# Generator.net
KiCad netlist of a schematic drawn in Altium Designer
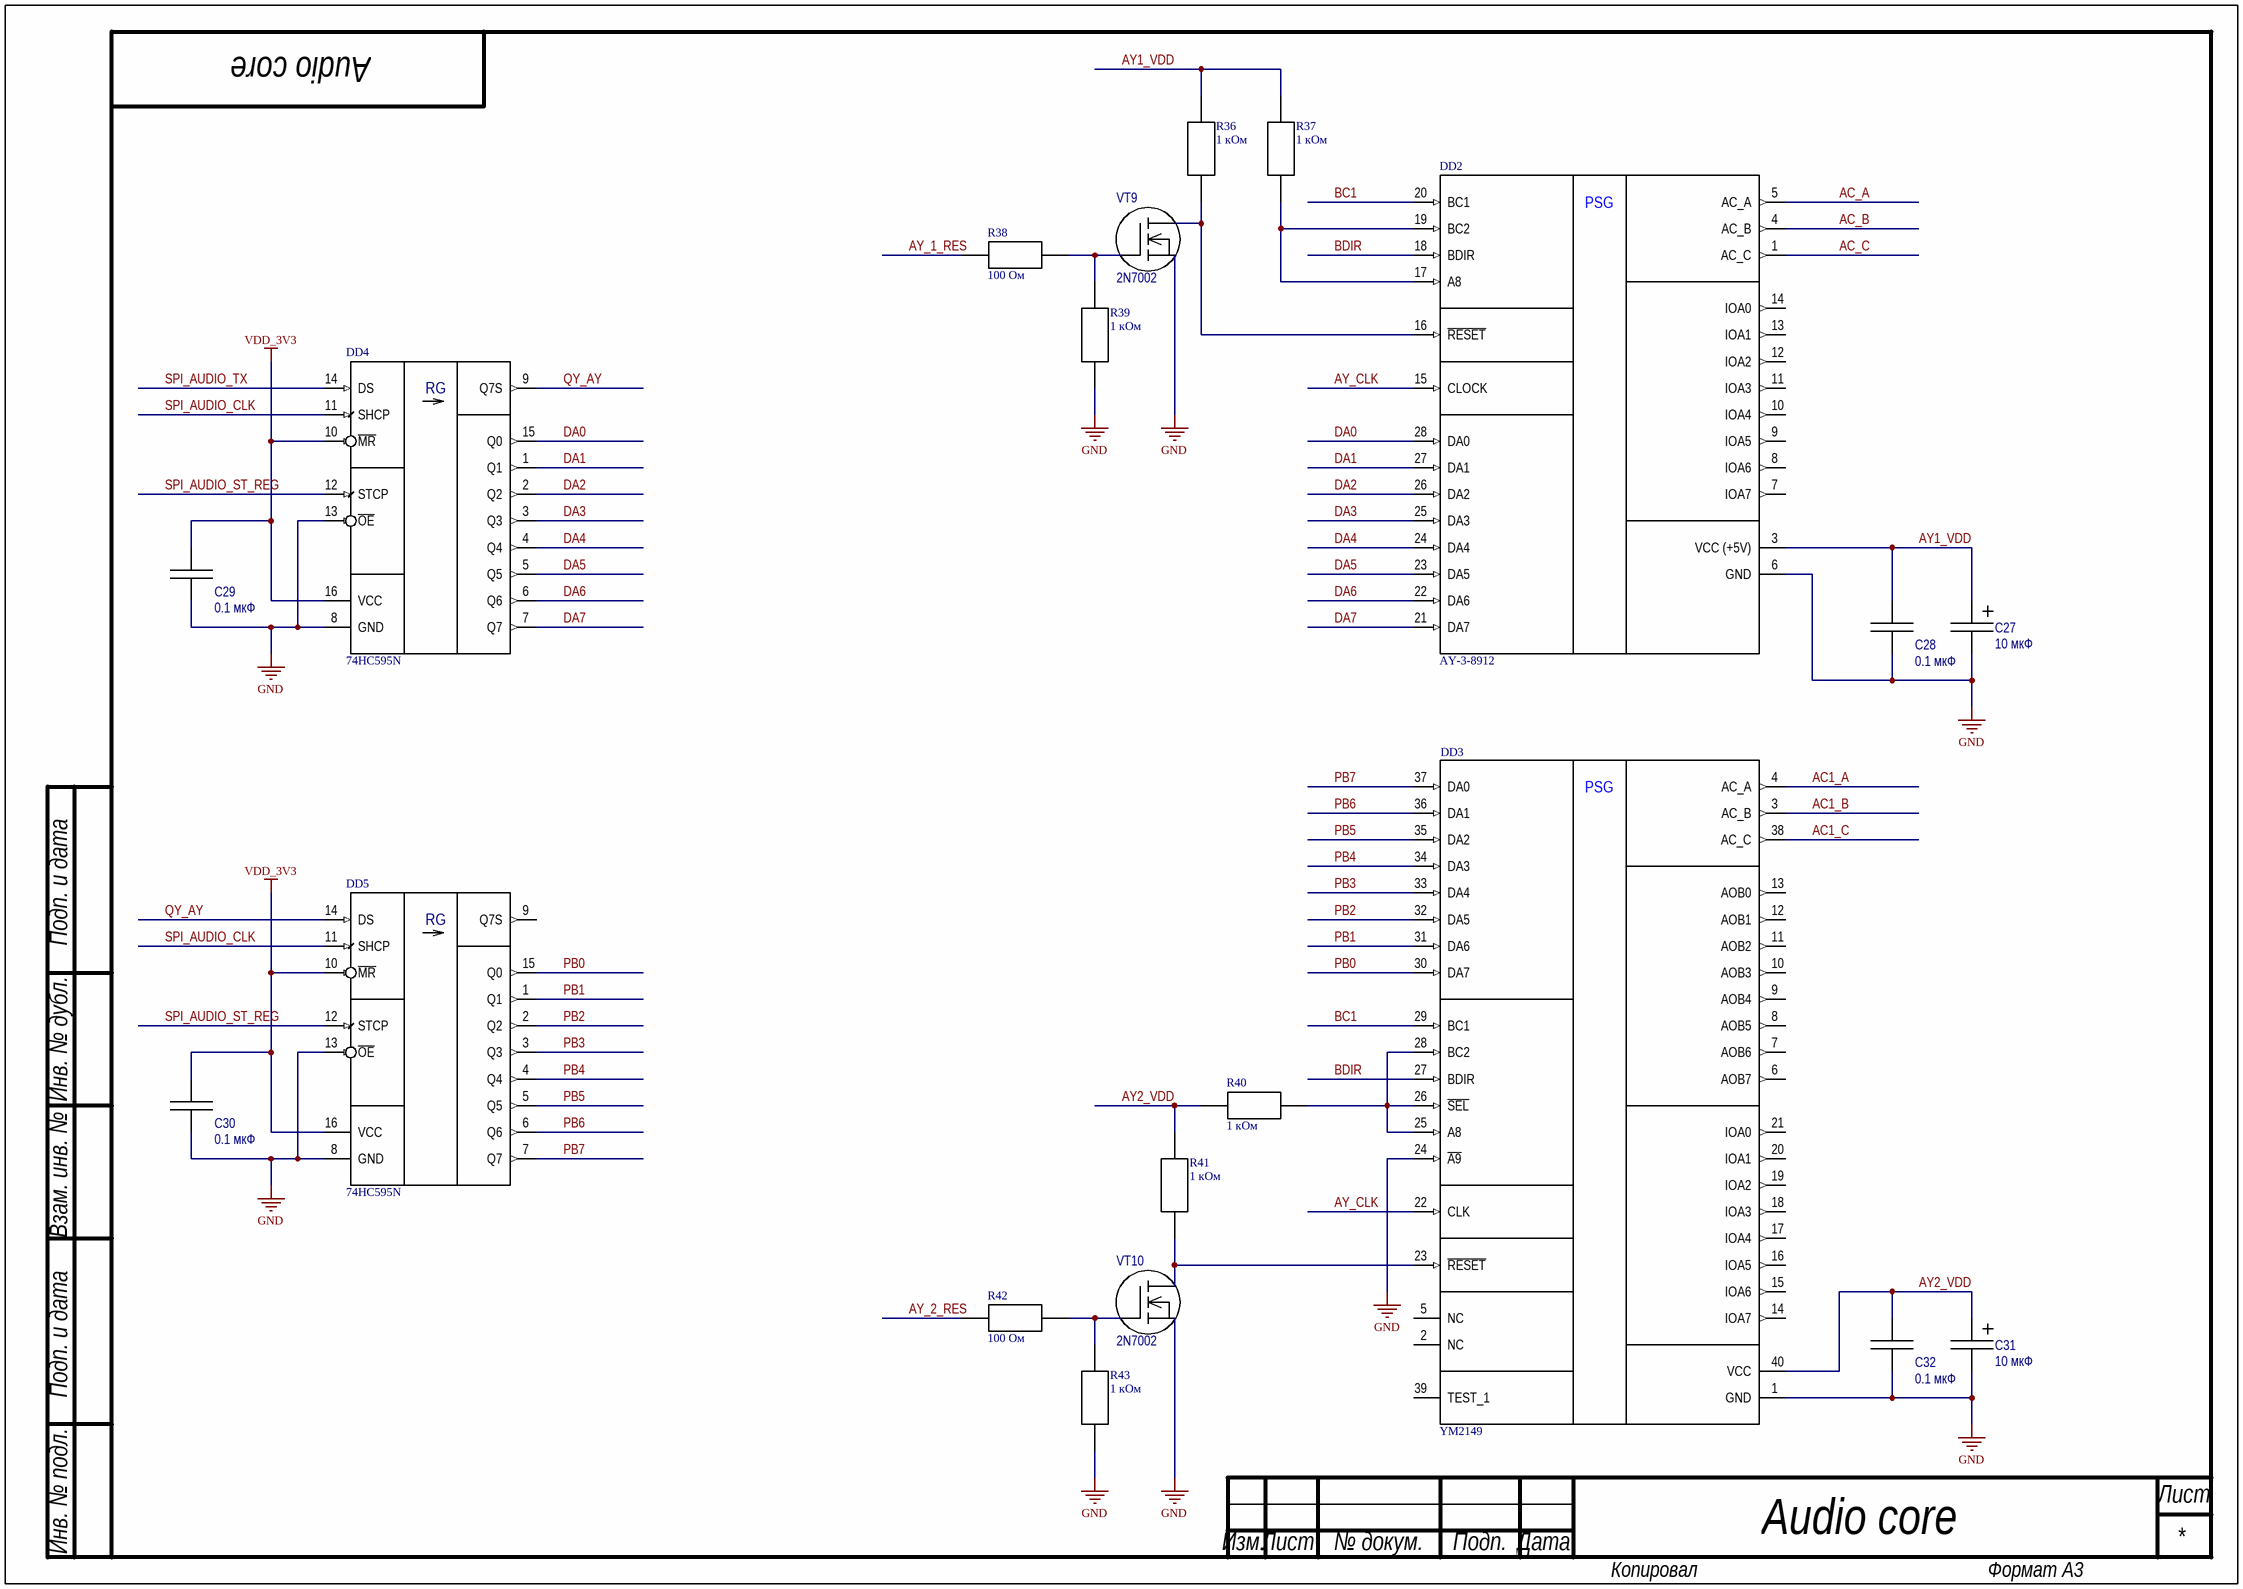
[diagram p0: Generator.SchDoc]

(export (version "E")
  (design (tool "Eeschema 10.0.6"))
  (components
    (comp (ref "C27")
      (value "10 мкФ")
      (footprint "C TAN_C")
      (description "SMD Tantalium Capacitor C")
      (fields
        (field (name "TOLERANCE") "/Укажите допуск в процентах/")
        (field (name "MANUFACTURER") "/Укажите компанию-производителя/")
      )
      (libsource (lib "my_lib") (part "CAP TAN_C"))
    )
    (comp (ref "C28")
      (value "0.1 мкФ")
      (footprint "C 1206")
      (description "SMD Capacitor 1206")
      (fields
        (field (name "TOLERANCE") "/Укажите допуск в процентах/")
        (field (name "MANUFACTURER") "/Укажите компанию-производителя/")
      )
      (libsource (lib "my_lib") (part "CAP 1206"))
    )
    (comp (ref "C29")
      (value "0.1 мкФ")
      (footprint "C 1206")
      (description "SMD Capacitor 1206")
      (fields
        (field (name "TOLERANCE") "/Укажите допуск в процентах/")
        (field (name "MANUFACTURER") "/Укажите компанию-производителя/")
      )
      (libsource (lib "my_lib") (part "CAP 1206"))
    )
    (comp (ref "C30")
      (value "0.1 мкФ")
      (footprint "C 1206")
      (description "SMD Capacitor 1206")
      (fields
        (field (name "TOLERANCE") "/Укажите допуск в процентах/")
        (field (name "MANUFACTURER") "/Укажите компанию-производителя/")
      )
      (libsource (lib "my_lib") (part "CAP 1206"))
    )
    (comp (ref "C31")
      (value "10 мкФ")
      (footprint "C TAN_C")
      (description "SMD Tantalium Capacitor C")
      (fields
        (field (name "TOLERANCE") "/Укажите допуск в процентах/")
        (field (name "MANUFACTURER") "/Укажите компанию-производителя/")
      )
      (libsource (lib "my_lib") (part "CAP TAN_C"))
    )
    (comp (ref "C32")
      (value "0.1 мкФ")
      (footprint "C 1206")
      (description "SMD Capacitor 1206")
      (fields
        (field (name "TOLERANCE") "/Укажите допуск в процентах/")
        (field (name "MANUFACTURER") "/Укажите компанию-производителя/")
      )
      (libsource (lib "my_lib") (part "CAP 1206"))
    )
    (comp (ref "DD2") (value "AY-3-8912") (footprint "DIP-28") (libsource (lib "my_lib") (part "AY-3-8912")))
    (comp (ref "DD3") (value "YM2149") (footprint "DIP-40") (libsource (lib "my_lib") (part "YM2149")))
    (comp (ref "DD4") (value "74HC595N") (footprint "SO16") (libsource (lib "my_lib") (part "74HC595N")))
    (comp (ref "DD5") (value "74HC595N") (footprint "SO16") (libsource (lib "my_lib") (part "74HC595N")))
    (comp (ref "R36") (value "1 кОм") (footprint "RES 0805") (libsource (lib "my_lib") (part "RES 0805")))
    (comp (ref "R37") (value "1 кОм") (footprint "RES 0805") (libsource (lib "my_lib") (part "RES 0805")))
    (comp (ref "R38") (value "100 Ом") (footprint "RES 0805") (libsource (lib "my_lib") (part "RES 0805")))
    (comp (ref "R39") (value "1 кОм") (footprint "RES 0805") (libsource (lib "my_lib") (part "RES 0805")))
    (comp (ref "R40") (value "1 кОм") (footprint "RES 0805") (libsource (lib "my_lib") (part "RES 0805")))
    (comp (ref "R41") (value "1 кОм") (footprint "RES 0805") (libsource (lib "my_lib") (part "RES 0805")))
    (comp (ref "R42") (value "100 Ом") (footprint "RES 0805") (libsource (lib "my_lib") (part "RES 0805")))
    (comp (ref "R43") (value "1 кОм") (footprint "RES 0805") (libsource (lib "my_lib") (part "RES 0805")))
    (comp (ref "VT9")
      (value "2N7002")
      (footprint "SOT-23")
      (description "60 V, 300 mA N-channel Trench MOSFET")
      (fields (field (name "MANUFACTURER") "NXP"))
      (libsource (lib "my_lib") (part "2N7002"))
    )
    (comp (ref "VT10")
      (value "2N7002")
      (footprint "SOT-23")
      (description "60 V, 300 mA N-channel Trench MOSFET")
      (fields (field (name "MANUFACTURER") "NXP"))
      (libsource (lib "my_lib") (part "2N7002"))
    )
  )
  (nets
    (net (code "1") (name "/AC1_A") (class "Default")
      (node (ref "DD3") (pin "4") (pinfunction "AC_A_4") (pintype "output"))
    )
    (net (code "2") (name "/AC1_B") (class "Default")
      (node (ref "DD3") (pin "3") (pinfunction "AC_B_3") (pintype "output"))
    )
    (net (code "3") (name "/AC1_C") (class "Default")
      (node (ref "DD3") (pin "38") (pinfunction "AC_C_38") (pintype "output"))
    )
    (net (code "4") (name "/AC_A") (class "Default")
      (node (ref "DD2") (pin "5") (pinfunction "AC_A_5") (pintype "output"))
    )
    (net (code "5") (name "/AC_B") (class "Default")
      (node (ref "DD2") (pin "4") (pinfunction "AC_B_4") (pintype "output"))
    )
    (net (code "6") (name "/AC_C") (class "Default")
      (node (ref "DD2") (pin "1") (pinfunction "AC_C_1") (pintype "output"))
    )
    (net (code "7") (name "/AY1_VDD") (class "Default")
      (node (ref "C27") (pin "1") (pinfunction "1_1") (pintype "passive"))
      (node (ref "C28") (pin "1") (pinfunction "1_1") (pintype "passive"))
      (node (ref "DD2") (pin "3") (pinfunction "VCC_(+5V)_3") (pintype "power_in"))
      (node (ref "R36") (pin "2") (pinfunction "2_2") (pintype "passive"))
      (node (ref "R37") (pin "1") (pinfunction "1_1") (pintype "passive"))
    )
    (net (code "8") (name "/AY2_VDD") (class "Default")
      (node (ref "C31") (pin "1") (pinfunction "1_1") (pintype "passive"))
      (node (ref "C32") (pin "1") (pinfunction "1_1") (pintype "passive"))
      (node (ref "DD3") (pin "40") (pinfunction "VCC_40") (pintype "power_in"))
      (node (ref "R40") (pin "2") (pinfunction "2_2") (pintype "passive"))
      (node (ref "R41") (pin "2") (pinfunction "2_2") (pintype "passive"))
    )
    (net (code "9") (name "/AY_1_RES") (class "Default")
      (node (ref "R38") (pin "1") (pinfunction "1_1") (pintype "passive"))
    )
    (net (code "10") (name "/AY_2_RES") (class "Default")
      (node (ref "R42") (pin "1") (pinfunction "1_1") (pintype "passive"))
    )
    (net (code "11") (name "/AY_CLK") (class "Default")
      (node (ref "DD2") (pin "15") (pinfunction "CLOCK_15") (pintype "input"))
      (node (ref "DD3") (pin "22") (pinfunction "CLK_22") (pintype "input"))
    )
    (net (code "12") (name "/BC1") (class "Default")
      (node (ref "DD2") (pin "20") (pinfunction "BC1_20") (pintype "input"))
      (node (ref "DD3") (pin "29") (pinfunction "BC1_29") (pintype "input"))
    )
    (net (code "13") (name "/BDIR") (class "Default")
      (node (ref "DD2") (pin "18") (pinfunction "BDIR_18") (pintype "input"))
      (node (ref "DD3") (pin "27") (pinfunction "BDIR_27") (pintype "input"))
    )
    (net (code "14") (name "/DA0") (class "Default")
      (node (ref "DD2") (pin "28") (pinfunction "DA0_28") (pintype "input"))
      (node (ref "DD4") (pin "15") (pinfunction "Q0_15") (pintype "output"))
    )
    (net (code "15") (name "/DA1") (class "Default")
      (node (ref "DD2") (pin "27") (pinfunction "DA1_27") (pintype "input"))
      (node (ref "DD4") (pin "1") (pinfunction "Q1_1") (pintype "output"))
    )
    (net (code "16") (name "/DA2") (class "Default")
      (node (ref "DD2") (pin "26") (pinfunction "DA2_26") (pintype "input"))
      (node (ref "DD4") (pin "2") (pinfunction "Q2_2") (pintype "output"))
    )
    (net (code "17") (name "/DA3") (class "Default")
      (node (ref "DD2") (pin "25") (pinfunction "DA3_25") (pintype "input"))
      (node (ref "DD4") (pin "3") (pinfunction "Q3_3") (pintype "output"))
    )
    (net (code "18") (name "/DA4") (class "Default")
      (node (ref "DD2") (pin "24") (pinfunction "DA4_24") (pintype "input"))
      (node (ref "DD4") (pin "4") (pinfunction "Q4_4") (pintype "output"))
    )
    (net (code "19") (name "/DA5") (class "Default")
      (node (ref "DD2") (pin "23") (pinfunction "DA5_23") (pintype "input"))
      (node (ref "DD4") (pin "5") (pinfunction "Q5_5") (pintype "output"))
    )
    (net (code "20") (name "/DA6") (class "Default")
      (node (ref "DD2") (pin "22") (pinfunction "DA6_22") (pintype "input"))
      (node (ref "DD4") (pin "6") (pinfunction "Q6_6") (pintype "output"))
    )
    (net (code "21") (name "/DA7") (class "Default")
      (node (ref "DD2") (pin "21") (pinfunction "DA7_21") (pintype "input"))
      (node (ref "DD4") (pin "7") (pinfunction "Q7_7") (pintype "output"))
    )
    (net (code "22") (name "/PB0") (class "Default")
      (node (ref "DD3") (pin "30") (pinfunction "DA7_30") (pintype "input"))
      (node (ref "DD5") (pin "15") (pinfunction "Q0_15") (pintype "output"))
    )
    (net (code "23") (name "/PB1") (class "Default")
      (node (ref "DD3") (pin "31") (pinfunction "DA6_31") (pintype "input"))
      (node (ref "DD5") (pin "1") (pinfunction "Q1_1") (pintype "output"))
    )
    (net (code "24") (name "/PB2") (class "Default")
      (node (ref "DD3") (pin "32") (pinfunction "DA5_32") (pintype "input"))
      (node (ref "DD5") (pin "2") (pinfunction "Q2_2") (pintype "output"))
    )
    (net (code "25") (name "/PB3") (class "Default")
      (node (ref "DD3") (pin "33") (pinfunction "DA4_33") (pintype "input"))
      (node (ref "DD5") (pin "3") (pinfunction "Q3_3") (pintype "output"))
    )
    (net (code "26") (name "/PB4") (class "Default")
      (node (ref "DD3") (pin "34") (pinfunction "DA3_34") (pintype "input"))
      (node (ref "DD5") (pin "4") (pinfunction "Q4_4") (pintype "output"))
    )
    (net (code "27") (name "/PB5") (class "Default")
      (node (ref "DD3") (pin "35") (pinfunction "DA2_35") (pintype "input"))
      (node (ref "DD5") (pin "5") (pinfunction "Q5_5") (pintype "output"))
    )
    (net (code "28") (name "/PB6") (class "Default")
      (node (ref "DD3") (pin "36") (pinfunction "DA1_36") (pintype "input"))
      (node (ref "DD5") (pin "6") (pinfunction "Q6_6") (pintype "output"))
    )
    (net (code "29") (name "/PB7") (class "Default")
      (node (ref "DD3") (pin "37") (pinfunction "DA0_37") (pintype "input"))
      (node (ref "DD5") (pin "7") (pinfunction "Q7_7") (pintype "output"))
    )
    (net (code "30") (name "/QY_AY") (class "Default")
      (node (ref "DD4") (pin "9") (pinfunction "Q7S_9") (pintype "output"))
      (node (ref "DD5") (pin "14") (pinfunction "DS_14") (pintype "input"))
    )
    (net (code "31") (name "/SPI_AUDIO_CLK") (class "Default")
      (node (ref "DD4") (pin "11") (pinfunction "SHCP_11") (pintype "input"))
      (node (ref "DD5") (pin "11") (pinfunction "SHCP_11") (pintype "input"))
    )
    (net (code "32") (name "/SPI_AUDIO_ST_REG") (class "Default")
      (node (ref "DD4") (pin "12") (pinfunction "STCP_12") (pintype "input"))
      (node (ref "DD5") (pin "12") (pinfunction "STCP_12") (pintype "input"))
    )
    (net (code "33") (name "/SPI_AUDIO_TX") (class "Default")
      (node (ref "DD4") (pin "14") (pinfunction "DS_14") (pintype "input"))
    )
    (net (code "34") (name "GND") (class "Default")
      (node (ref "C27") (pin "2") (pinfunction "2_2") (pintype "passive"))
      (node (ref "C28") (pin "2") (pinfunction "2_2") (pintype "passive"))
      (node (ref "C29") (pin "2") (pinfunction "2_2") (pintype "passive"))
      (node (ref "C30") (pin "2") (pinfunction "2_2") (pintype "passive"))
      (node (ref "C31") (pin "2") (pinfunction "2_2") (pintype "passive"))
      (node (ref "C32") (pin "2") (pinfunction "2_2") (pintype "passive"))
      (node (ref "DD2") (pin "6") (pinfunction "GND_6") (pintype "power_in"))
      (node (ref "DD3") (pin "1") (pinfunction "GND_1") (pintype "power_in"))
      (node (ref "DD3") (pin "24") (pinfunction "~{A9}_24") (pintype "input"))
      (node (ref "DD4") (pin "13") (pinfunction "~{OE}_13") (pintype "input"))
      (node (ref "DD4") (pin "8") (pinfunction "GND_8") (pintype "power_in"))
      (node (ref "DD5") (pin "13") (pinfunction "~{OE}_13") (pintype "input"))
      (node (ref "DD5") (pin "8") (pinfunction "GND_8") (pintype "power_in"))
      (node (ref "R39") (pin "1") (pinfunction "1_1") (pintype "passive"))
      (node (ref "R43") (pin "1") (pinfunction "1_1") (pintype "passive"))
      (node (ref "VT10") (pin "2") (pinfunction "S_2") (pintype "passive"))
      (node (ref "VT9") (pin "2") (pinfunction "S_2") (pintype "passive"))
    )
    (net (code "35") (name "Net-(DD2-A8)") (class "Default")
      (node (ref "DD2") (pin "17") (pinfunction "A8_17") (pintype "input"))
      (node (ref "DD2") (pin "19") (pinfunction "BC2_19") (pintype "input"))
      (node (ref "R37") (pin "2") (pinfunction "2_2") (pintype "passive"))
    )
    (net (code "36") (name "Net-(DD2-~{RESET})") (class "Default")
      (node (ref "DD2") (pin "16") (pinfunction "~{RESET}_16") (pintype "input"))
      (node (ref "R36") (pin "1") (pinfunction "1_1") (pintype "passive"))
      (node (ref "VT9") (pin "3") (pinfunction "D_3") (pintype "passive"))
    )
    (net (code "37") (name "Net-(DD3-A8)") (class "Default")
      (node (ref "DD3") (pin "25") (pinfunction "A8_25") (pintype "input"))
      (node (ref "DD3") (pin "26") (pinfunction "~{SEL}_26") (pintype "input"))
      (node (ref "DD3") (pin "28") (pinfunction "BC2_28") (pintype "input"))
      (node (ref "R40") (pin "1") (pinfunction "1_1") (pintype "passive"))
    )
    (net (code "38") (name "Net-(DD3-~{RESET})") (class "Default")
      (node (ref "DD3") (pin "23") (pinfunction "~{RESET}_23") (pintype "input"))
      (node (ref "R41") (pin "1") (pinfunction "1_1") (pintype "passive"))
      (node (ref "VT10") (pin "3") (pinfunction "D_3") (pintype "passive"))
    )
    (net (code "39") (name "Net-(VT9-G)") (class "Default")
      (node (ref "R38") (pin "2") (pinfunction "2_2") (pintype "passive"))
      (node (ref "R39") (pin "2") (pinfunction "2_2") (pintype "passive"))
      (node (ref "VT9") (pin "1") (pinfunction "G_1") (pintype "passive"))
    )
    (net (code "40") (name "Net-(VT10-G)") (class "Default")
      (node (ref "R42") (pin "2") (pinfunction "2_2") (pintype "passive"))
      (node (ref "R43") (pin "2") (pinfunction "2_2") (pintype "passive"))
      (node (ref "VT10") (pin "1") (pinfunction "G_1") (pintype "passive"))
    )
    (net (code "41") (name "VDD_3V3") (class "Default")
      (node (ref "C29") (pin "1") (pinfunction "1_1") (pintype "passive"))
      (node (ref "C30") (pin "1") (pinfunction "1_1") (pintype "passive"))
      (node (ref "DD4") (pin "10") (pinfunction "~{MR}_10") (pintype "input"))
      (node (ref "DD4") (pin "16") (pinfunction "VCC_16") (pintype "power_in"))
      (node (ref "DD5") (pin "10") (pinfunction "~{MR}_10") (pintype "input"))
      (node (ref "DD5") (pin "16") (pinfunction "VCC_16") (pintype "power_in"))
    )
    (net (code "42") (name "unconnected-(DD2-IOA0-Pad14)") (class "Default")
      (node (ref "DD2") (pin "14") (pinfunction "IOA0_14") (pintype "output"))
    )
    (net (code "43") (name "unconnected-(DD2-IOA1-Pad13)") (class "Default")
      (node (ref "DD2") (pin "13") (pinfunction "IOA1_13") (pintype "output"))
    )
    (net (code "44") (name "unconnected-(DD2-IOA2-Pad12)") (class "Default")
      (node (ref "DD2") (pin "12") (pinfunction "IOA2_12") (pintype "output"))
    )
    (net (code "45") (name "unconnected-(DD2-IOA3-Pad11)") (class "Default")
      (node (ref "DD2") (pin "11") (pinfunction "IOA3_11") (pintype "output"))
    )
    (net (code "46") (name "unconnected-(DD2-IOA4-Pad10)") (class "Default")
      (node (ref "DD2") (pin "10") (pinfunction "IOA4_10") (pintype "output"))
    )
    (net (code "47") (name "unconnected-(DD2-IOA5-Pad9)") (class "Default")
      (node (ref "DD2") (pin "9") (pinfunction "IOA5_9") (pintype "output"))
    )
    (net (code "48") (name "unconnected-(DD2-IOA6-Pad8)") (class "Default")
      (node (ref "DD2") (pin "8") (pinfunction "IOA6_8") (pintype "output"))
    )
    (net (code "49") (name "unconnected-(DD2-IOA7-Pad7)") (class "Default")
      (node (ref "DD2") (pin "7") (pinfunction "IOA7_7") (pintype "output"))
    )
    (net (code "50") (name "unconnected-(DD3-AOB0-Pad13)") (class "Default")
      (node (ref "DD3") (pin "13") (pinfunction "AOB0_13") (pintype "output"))
    )
    (net (code "51") (name "unconnected-(DD3-AOB1-Pad12)") (class "Default")
      (node (ref "DD3") (pin "12") (pinfunction "AOB1_12") (pintype "output"))
    )
    (net (code "52") (name "unconnected-(DD3-AOB2-Pad11)") (class "Default")
      (node (ref "DD3") (pin "11") (pinfunction "AOB2_11") (pintype "output"))
    )
    (net (code "53") (name "unconnected-(DD3-AOB3-Pad10)") (class "Default")
      (node (ref "DD3") (pin "10") (pinfunction "AOB3_10") (pintype "output"))
    )
    (net (code "54") (name "unconnected-(DD3-AOB4-Pad9)") (class "Default")
      (node (ref "DD3") (pin "9") (pinfunction "AOB4_9") (pintype "output"))
    )
    (net (code "55") (name "unconnected-(DD3-AOB5-Pad8)") (class "Default")
      (node (ref "DD3") (pin "8") (pinfunction "AOB5_8") (pintype "output"))
    )
    (net (code "56") (name "unconnected-(DD3-AOB6-Pad7)") (class "Default")
      (node (ref "DD3") (pin "7") (pinfunction "AOB6_7") (pintype "output"))
    )
    (net (code "57") (name "unconnected-(DD3-AOB7-Pad6)") (class "Default")
      (node (ref "DD3") (pin "6") (pinfunction "AOB7_6") (pintype "output"))
    )
    (net (code "58") (name "unconnected-(DD3-IOA0-Pad21)") (class "Default")
      (node (ref "DD3") (pin "21") (pinfunction "IOA0_21") (pintype "output"))
    )
    (net (code "59") (name "unconnected-(DD3-IOA1-Pad20)") (class "Default")
      (node (ref "DD3") (pin "20") (pinfunction "IOA1_20") (pintype "output"))
    )
    (net (code "60") (name "unconnected-(DD3-IOA2-Pad19)") (class "Default")
      (node (ref "DD3") (pin "19") (pinfunction "IOA2_19") (pintype "output"))
    )
    (net (code "61") (name "unconnected-(DD3-IOA3-Pad18)") (class "Default")
      (node (ref "DD3") (pin "18") (pinfunction "IOA3_18") (pintype "output"))
    )
    (net (code "62") (name "unconnected-(DD3-IOA4-Pad17)") (class "Default")
      (node (ref "DD3") (pin "17") (pinfunction "IOA4_17") (pintype "output"))
    )
    (net (code "63") (name "unconnected-(DD3-IOA5-Pad16)") (class "Default")
      (node (ref "DD3") (pin "16") (pinfunction "IOA5_16") (pintype "output"))
    )
    (net (code "64") (name "unconnected-(DD3-IOA6-Pad15)") (class "Default")
      (node (ref "DD3") (pin "15") (pinfunction "IOA6_15") (pintype "output"))
    )
    (net (code "65") (name "unconnected-(DD3-IOA7-Pad14)") (class "Default")
      (node (ref "DD3") (pin "14") (pinfunction "IOA7_14") (pintype "output"))
    )
    (net (code "66") (name "unconnected-(DD3-NC-Pad2)") (class "Default")
      (node (ref "DD3") (pin "2") (pinfunction "NC_2") (pintype "passive"))
    )
    (net (code "67") (name "unconnected-(DD3-NC-Pad5)") (class "Default")
      (node (ref "DD3") (pin "5") (pinfunction "NC_5") (pintype "passive"))
    )
    (net (code "68") (name "unconnected-(DD3-TEST_1-Pad39)") (class "Default")
      (node (ref "DD3") (pin "39") (pinfunction "TEST_1_39") (pintype "passive"))
    )
    (net (code "69") (name "unconnected-(DD5-Q7S-Pad9)") (class "Default")
      (node (ref "DD5") (pin "9") (pinfunction "Q7S_9") (pintype "output"))
    )
  )
)
